# led_driver.net
KiCad netlist of a schematic drawn in Altium Designer
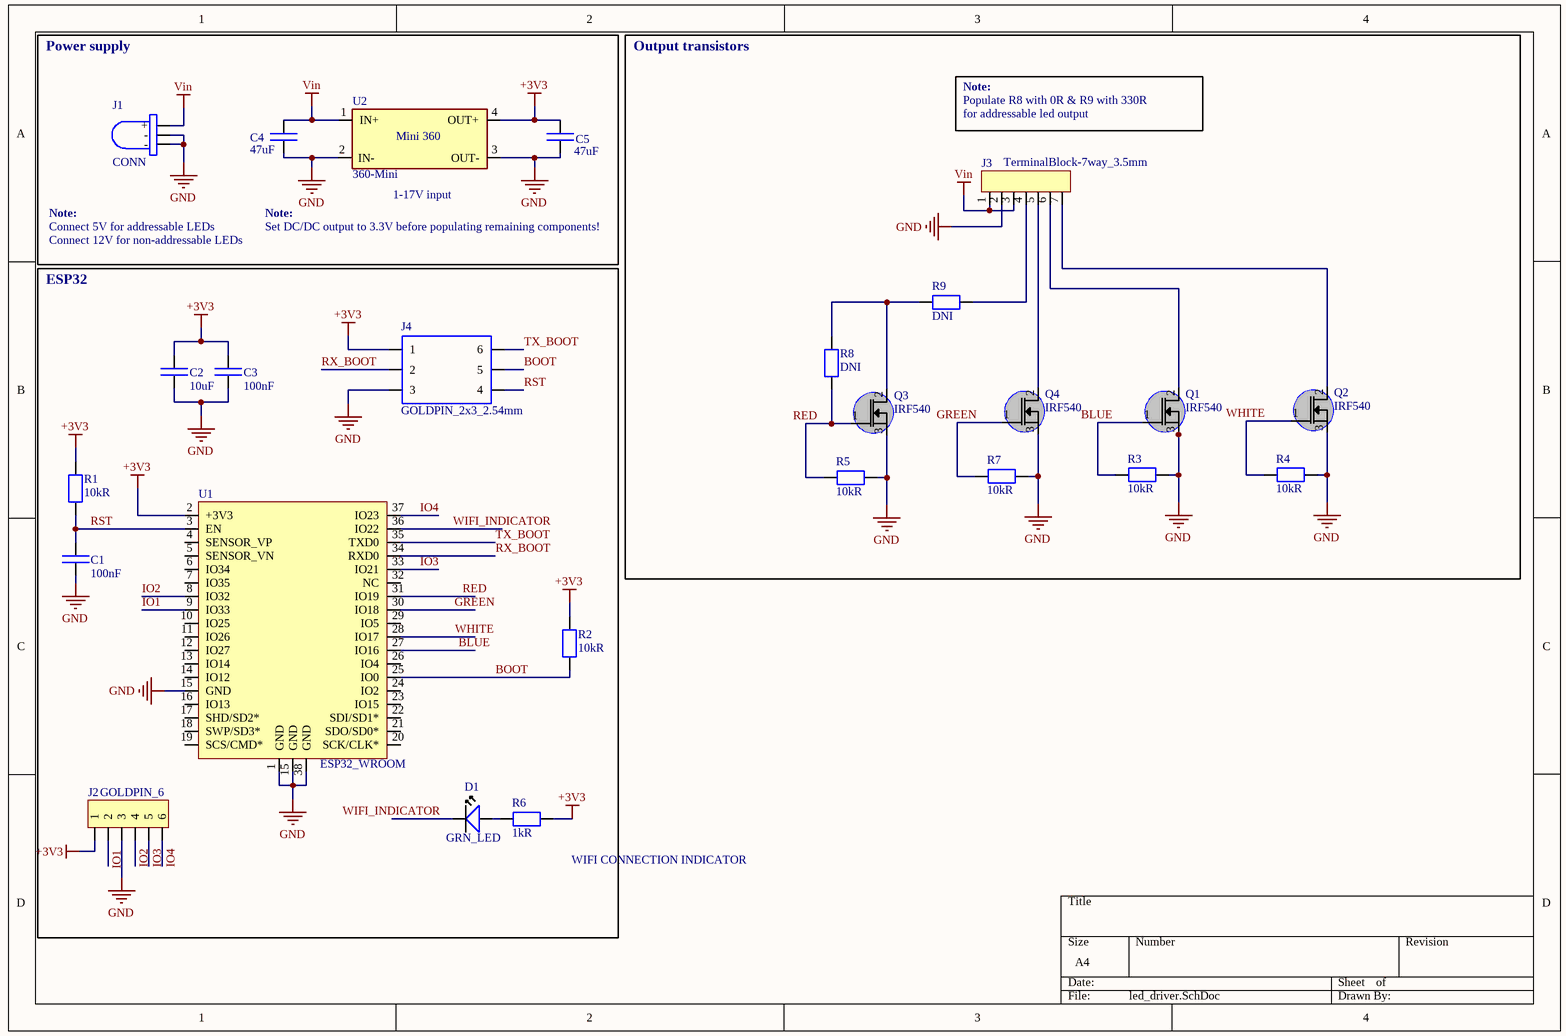
[diagram p0: led_driver.SchDoc]

(export (version "E")
  (design (tool "Eeschema 10.0.6"))
  (components
    (comp (ref "C1") (value "100nF") (footprint "C0603") (libsource (lib "przem_lib") (part "Cap_SMD")))
    (comp (ref "C2") (value "10uF") (footprint "C0603") (libsource (lib "przem_lib") (part "Cap_SMD")))
    (comp (ref "C3") (value "100nF") (footprint "C0603") (libsource (lib "przem_lib") (part "Cap_SMD")))
    (comp (ref "C4") (value "47uF") (footprint "C0805") (libsource (lib "przem_lib") (part "Cap_SMD")))
    (comp (ref "C5") (value "47uF") (footprint "C0805") (libsource (lib "przem_lib") (part "Cap_SMD")))
    (comp (ref "D1") (value "GRN_LED") (footprint "G_LED0805") (libsource (lib "przem_lib") (part "GRN_LED")))
    (comp (ref "J1") (value "CONN") (footprint "BarrelJack") (libsource (lib "przem_lib") (part "DC-barrel")))
    (comp (ref "J2")
      (value "GOLDPIN_6")
      (footprint "pin_header_6_male")
      (libsource (lib "przem_lib") (part "GOLDPIN_6"))
    )
    (comp (ref "J3")
      (value "TerminalBlock-7way_3.5mm")
      (footprint "TerminalBlock-7way")
      (libsource (lib "przem_lib") (part "TerminalBlock-7way_3.5mm"))
    )
    (comp (ref "J4")
      (value "GOLDPIN_2x3_2.54mm")
      (footprint "PIN_HEADER_2x3_2.54mm")
      (libsource (lib "przem_lib") (part "GOLDPIN_2x3_2.54mm"))
    )
    (comp (ref "Q1") (value "IRF540") (footprint "IRF540") (libsource (lib "przem_lib") (part "IRF540")))
    (comp (ref "Q2") (value "IRF540") (footprint "IRF540") (libsource (lib "przem_lib") (part "IRF540")))
    (comp (ref "Q3") (value "IRF540") (footprint "IRF540") (libsource (lib "przem_lib") (part "IRF540")))
    (comp (ref "Q4") (value "IRF540") (footprint "IRF540") (libsource (lib "przem_lib") (part "IRF540")))
    (comp (ref "R1") (value "10kR") (footprint "R0603") (libsource (lib "przem_lib") (part "Res")))
    (comp (ref "R2") (value "10kR") (footprint "R0603") (libsource (lib "przem_lib") (part "Res")))
    (comp (ref "R3") (value "10kR") (footprint "R0603") (libsource (lib "przem_lib") (part "Res")))
    (comp (ref "R4") (value "10kR") (footprint "R0603") (libsource (lib "przem_lib") (part "Res")))
    (comp (ref "R5") (value "10kR") (footprint "R0603") (libsource (lib "przem_lib") (part "Res")))
    (comp (ref "R6") (value "1kR") (footprint "R0603") (libsource (lib "przem_lib") (part "Res")))
    (comp (ref "R7") (value "10kR") (footprint "R0603") (libsource (lib "przem_lib") (part "Res")))
    (comp (ref "R8") (value "DNI") (footprint "R0603") (libsource (lib "przem_lib") (part "Res")))
    (comp (ref "R9") (value "DNI") (footprint "R0805") (libsource (lib "przem_lib") (part "Res")))
    (comp (ref "U1")
      (value "ESP32_WROOM")
      (footprint "ESP32-WROOM-32")
      (libsource (lib "przem_lib") (part "ESP32_WROOM"))
    )
    (comp (ref "U2")
      (value "360-Mini")
      (footprint "DC-mini360-smd")
      (libsource (lib "przem_lib") (part "360-Mini"))
    )
  )
  (nets
    (net (code "1") (name "+3V3") (class "Default")
      (node (ref "C2") (pin "2") (pinfunction "2_2") (pintype "passive"))
      (node (ref "C3") (pin "2") (pinfunction "2_2") (pintype "passive"))
      (node (ref "C5") (pin "2") (pinfunction "2_2") (pintype "passive"))
      (node (ref "J2") (pin "1") (pinfunction "1_1") (pintype "passive"))
      (node (ref "J4") (pin "1") (pinfunction "1_1") (pintype "passive"))
      (node (ref "R1") (pin "2") (pinfunction "2_2") (pintype "passive"))
      (node (ref "R2") (pin "2") (pinfunction "2_2") (pintype "passive"))
      (node (ref "R6") (pin "2") (pinfunction "2_2") (pintype "passive"))
      (node (ref "U1") (pin "2") (pinfunction "+3V3_2") (pintype "passive"))
      (node (ref "U2") (pin "4") (pinfunction "OUT+_4") (pintype "passive"))
    )
    (net (code "2") (name "/BLUE") (class "Default")
      (node (ref "Q1") (pin "1") (pinfunction "G_1") (pintype "passive"))
      (node (ref "R3") (pin "2") (pinfunction "2_2") (pintype "passive"))
      (node (ref "U1") (pin "27") (pinfunction "IO16_27") (pintype "passive"))
    )
    (net (code "3") (name "/BOOT") (class "Default")
      (node (ref "J4") (pin "5") (pinfunction "5_5") (pintype "passive"))
      (node (ref "R2") (pin "1") (pinfunction "1_1") (pintype "passive"))
      (node (ref "U1") (pin "25") (pinfunction "IO0_25") (pintype "passive"))
    )
    (net (code "4") (name "/GREEN") (class "Default")
      (node (ref "Q4") (pin "1") (pinfunction "G_1") (pintype "passive"))
      (node (ref "R7") (pin "2") (pinfunction "2_2") (pintype "passive"))
      (node (ref "U1") (pin "30") (pinfunction "IO18_30") (pintype "passive"))
    )
    (net (code "5") (name "/IO1") (class "Default")
      (node (ref "J2") (pin "2") (pinfunction "2_2") (pintype "passive"))
      (node (ref "U1") (pin "9") (pinfunction "IO33_9") (pintype "passive"))
    )
    (net (code "6") (name "/IO2") (class "Default")
      (node (ref "J2") (pin "4") (pinfunction "4_4") (pintype "passive"))
      (node (ref "U1") (pin "8") (pinfunction "IO32_8") (pintype "passive"))
    )
    (net (code "7") (name "/IO3") (class "Default")
      (node (ref "J2") (pin "5") (pinfunction "5_5") (pintype "passive"))
      (node (ref "U1") (pin "33") (pinfunction "IO21_33") (pintype "passive"))
    )
    (net (code "8") (name "/IO4") (class "Default")
      (node (ref "J2") (pin "6") (pinfunction "6_6") (pintype "passive"))
      (node (ref "U1") (pin "37") (pinfunction "IO23_37") (pintype "passive"))
    )
    (net (code "9") (name "/RED") (class "Default")
      (node (ref "Q3") (pin "1") (pinfunction "G_1") (pintype "passive"))
      (node (ref "R5") (pin "2") (pinfunction "2_2") (pintype "passive"))
      (node (ref "R8") (pin "2") (pinfunction "2_2") (pintype "passive"))
      (node (ref "U1") (pin "31") (pinfunction "IO19_31") (pintype "passive"))
    )
    (net (code "10") (name "/RST") (class "Default")
      (node (ref "C1") (pin "1") (pinfunction "1_1") (pintype "passive"))
      (node (ref "J4") (pin "4") (pinfunction "4_4") (pintype "passive"))
      (node (ref "R1") (pin "1") (pinfunction "1_1") (pintype "passive"))
      (node (ref "U1") (pin "3") (pinfunction "EN_3") (pintype "passive"))
    )
    (net (code "11") (name "/RX_BOOT") (class "Default")
      (node (ref "J4") (pin "2") (pinfunction "2_2") (pintype "passive"))
      (node (ref "U1") (pin "34") (pinfunction "RXD0_34") (pintype "passive"))
    )
    (net (code "12") (name "/TX_BOOT") (class "Default")
      (node (ref "J4") (pin "6") (pinfunction "6_6") (pintype "passive"))
      (node (ref "U1") (pin "35") (pinfunction "TXD0_35") (pintype "passive"))
    )
    (net (code "13") (name "/WHITE") (class "Default")
      (node (ref "Q2") (pin "1") (pinfunction "G_1") (pintype "passive"))
      (node (ref "R4") (pin "2") (pinfunction "2_2") (pintype "passive"))
      (node (ref "U1") (pin "28") (pinfunction "IO17_28") (pintype "passive"))
    )
    (net (code "14") (name "/WIFI_INDICATOR") (class "Default")
      (node (ref "D1") (pin "K") (pinfunction "K_K") (pintype "passive"))
      (node (ref "U1") (pin "36") (pinfunction "IO22_36") (pintype "passive"))
    )
    (net (code "15") (name "GND") (class "Default")
      (node (ref "C1") (pin "2") (pinfunction "2_2") (pintype "passive"))
      (node (ref "C2") (pin "1") (pinfunction "1_1") (pintype "passive"))
      (node (ref "C3") (pin "1") (pinfunction "1_1") (pintype "passive"))
      (node (ref "C4") (pin "1") (pinfunction "1_1") (pintype "passive"))
      (node (ref "C5") (pin "1") (pinfunction "1_1") (pintype "passive"))
      (node (ref "J1") (pin "2") (pinfunction "-_2") (pintype "passive"))
      (node (ref "J1") (pin "3") (pinfunction "-_3") (pintype "passive"))
      (node (ref "J2") (pin "3") (pinfunction "3_3") (pintype "passive"))
      (node (ref "J3") (pin "2") (pinfunction "2_2") (pintype "passive"))
      (node (ref "J4") (pin "3") (pinfunction "3_3") (pintype "passive"))
      (node (ref "Q1") (pin "3") (pinfunction "3_3") (pintype "passive"))
      (node (ref "Q2") (pin "3") (pinfunction "3_3") (pintype "passive"))
      (node (ref "Q3") (pin "3") (pinfunction "3_3") (pintype "passive"))
      (node (ref "Q4") (pin "3") (pinfunction "3_3") (pintype "passive"))
      (node (ref "R3") (pin "1") (pinfunction "1_1") (pintype "passive"))
      (node (ref "R4") (pin "1") (pinfunction "1_1") (pintype "passive"))
      (node (ref "R5") (pin "1") (pinfunction "1_1") (pintype "passive"))
      (node (ref "R7") (pin "1") (pinfunction "1_1") (pintype "passive"))
      (node (ref "U1") (pin "1") (pinfunction "GND_1") (pintype "passive"))
      (node (ref "U1") (pin "15") (pinfunction "GND_15") (pintype "passive"))
      (node (ref "U1") (pin "38") (pinfunction "GND_38") (pintype "passive"))
      (node (ref "U2") (pin "2") (pinfunction "IN-_2") (pintype "passive"))
      (node (ref "U2") (pin "3") (pinfunction "OUT-_3") (pintype "passive"))
    )
    (net (code "16") (name "Net-(D1-PadA)") (class "Default")
      (node (ref "D1") (pin "A") (pinfunction "A_A") (pintype "passive"))
      (node (ref "R6") (pin "1") (pinfunction "1_1") (pintype "passive"))
    )
    (net (code "17") (name "Net-(J3-Pad4)") (class "Default")
      (node (ref "J3") (pin "4") (pinfunction "4_4") (pintype "passive"))
      (node (ref "R9") (pin "2") (pinfunction "2_2") (pintype "passive"))
    )
    (net (code "18") (name "Net-(J3-Pad5)") (class "Default")
      (node (ref "J3") (pin "5") (pinfunction "5_5") (pintype "passive"))
      (node (ref "Q4") (pin "2") (pinfunction "2_2") (pintype "passive"))
    )
    (net (code "19") (name "Net-(J3-Pad6)") (class "Default")
      (node (ref "J3") (pin "6") (pinfunction "6_6") (pintype "passive"))
      (node (ref "Q1") (pin "2") (pinfunction "2_2") (pintype "passive"))
    )
    (net (code "20") (name "Net-(J3-Pad7)") (class "Default")
      (node (ref "J3") (pin "7") (pinfunction "7_7") (pintype "passive"))
      (node (ref "Q2") (pin "2") (pinfunction "2_2") (pintype "passive"))
    )
    (net (code "21") (name "Net-(Q3-Pad2)") (class "Default")
      (node (ref "Q3") (pin "2") (pinfunction "2_2") (pintype "passive"))
      (node (ref "R8") (pin "1") (pinfunction "1_1") (pintype "passive"))
      (node (ref "R9") (pin "1") (pinfunction "1_1") (pintype "passive"))
    )
    (net (code "22") (name "Vin") (class "Default")
      (node (ref "C4") (pin "2") (pinfunction "2_2") (pintype "passive"))
      (node (ref "J1") (pin "1") (pinfunction "+_1") (pintype "passive"))
      (node (ref "J3") (pin "1") (pinfunction "1_1") (pintype "passive"))
      (node (ref "J3") (pin "3") (pinfunction "3_3") (pintype "passive"))
      (node (ref "U2") (pin "1") (pinfunction "IN+_1") (pintype "passive"))
    )
    (net (code "23") (name "unconnected-(U1-IO2-Pad24)") (class "Default")
      (node (ref "U1") (pin "24") (pinfunction "IO2_24") (pintype "passive"))
    )
    (net (code "24") (name "unconnected-(U1-IO4-Pad26)") (class "Default")
      (node (ref "U1") (pin "26") (pinfunction "IO4_26") (pintype "passive"))
    )
    (net (code "25") (name "unconnected-(U1-IO5-Pad29)") (class "Default")
      (node (ref "U1") (pin "29") (pinfunction "IO5_29") (pintype "passive"))
    )
    (net (code "26") (name "unconnected-(U1-IO12-Pad14)") (class "Default")
      (node (ref "U1") (pin "14") (pinfunction "IO12_14") (pintype "passive"))
    )
    (net (code "27") (name "unconnected-(U1-IO13-Pad16)") (class "Default")
      (node (ref "U1") (pin "16") (pinfunction "IO13_16") (pintype "passive"))
    )
    (net (code "28") (name "unconnected-(U1-IO14-Pad13)") (class "Default")
      (node (ref "U1") (pin "13") (pinfunction "IO14_13") (pintype "passive"))
    )
    (net (code "29") (name "unconnected-(U1-IO15-Pad23)") (class "Default")
      (node (ref "U1") (pin "23") (pinfunction "IO15_23") (pintype "passive"))
    )
    (net (code "30") (name "unconnected-(U1-IO25-Pad10)") (class "Default")
      (node (ref "U1") (pin "10") (pinfunction "IO25_10") (pintype "passive"))
    )
    (net (code "31") (name "unconnected-(U1-IO26-Pad11)") (class "Default")
      (node (ref "U1") (pin "11") (pinfunction "IO26_11") (pintype "passive"))
    )
    (net (code "32") (name "unconnected-(U1-IO27-Pad12)") (class "Default")
      (node (ref "U1") (pin "12") (pinfunction "IO27_12") (pintype "passive"))
    )
    (net (code "33") (name "unconnected-(U1-IO34-Pad6)") (class "Default")
      (node (ref "U1") (pin "6") (pinfunction "IO34_6") (pintype "passive"))
    )
    (net (code "34") (name "unconnected-(U1-IO35-Pad7)") (class "Default")
      (node (ref "U1") (pin "7") (pinfunction "IO35_7") (pintype "passive"))
    )
    (net (code "35") (name "unconnected-(U1-NC-Pad32)") (class "Default")
      (node (ref "U1") (pin "32") (pinfunction "NC_32") (pintype "passive"))
    )
    (net (code "36") (name "unconnected-(U1-SCK{slash}CLK*-Pad20)") (class "Default")
      (node (ref "U1") (pin "20") (pinfunction "SCK/CLK*_20") (pintype "passive"))
    )
    (net (code "37") (name "unconnected-(U1-SCS{slash}CMD*-Pad19)") (class "Default")
      (node (ref "U1") (pin "19") (pinfunction "SCS/CMD*_19") (pintype "passive"))
    )
    (net (code "38") (name "unconnected-(U1-SDI{slash}SD1*-Pad22)") (class "Default")
      (node (ref "U1") (pin "22") (pinfunction "SDI/SD1*_22") (pintype "passive"))
    )
    (net (code "39") (name "unconnected-(U1-SDO{slash}SD0*-Pad21)") (class "Default")
      (node (ref "U1") (pin "21") (pinfunction "SDO/SD0*_21") (pintype "passive"))
    )
    (net (code "40") (name "unconnected-(U1-SENSOR_VN-Pad5)") (class "Default")
      (node (ref "U1") (pin "5") (pinfunction "SENSOR_VN_5") (pintype "passive"))
    )
    (net (code "41") (name "unconnected-(U1-SENSOR_VP-Pad4)") (class "Default")
      (node (ref "U1") (pin "4") (pinfunction "SENSOR_VP_4") (pintype "passive"))
    )
    (net (code "42") (name "unconnected-(U1-SHD{slash}SD2*-Pad17)") (class "Default")
      (node (ref "U1") (pin "17") (pinfunction "SHD/SD2*_17") (pintype "passive"))
    )
    (net (code "43") (name "unconnected-(U1-SWP{slash}SD3*-Pad18)") (class "Default")
      (node (ref "U1") (pin "18") (pinfunction "SWP/SD3*_18") (pintype "passive"))
    )
  )
)
